# M105B.net
KiCad netlist of a schematic drawn in EAGLE
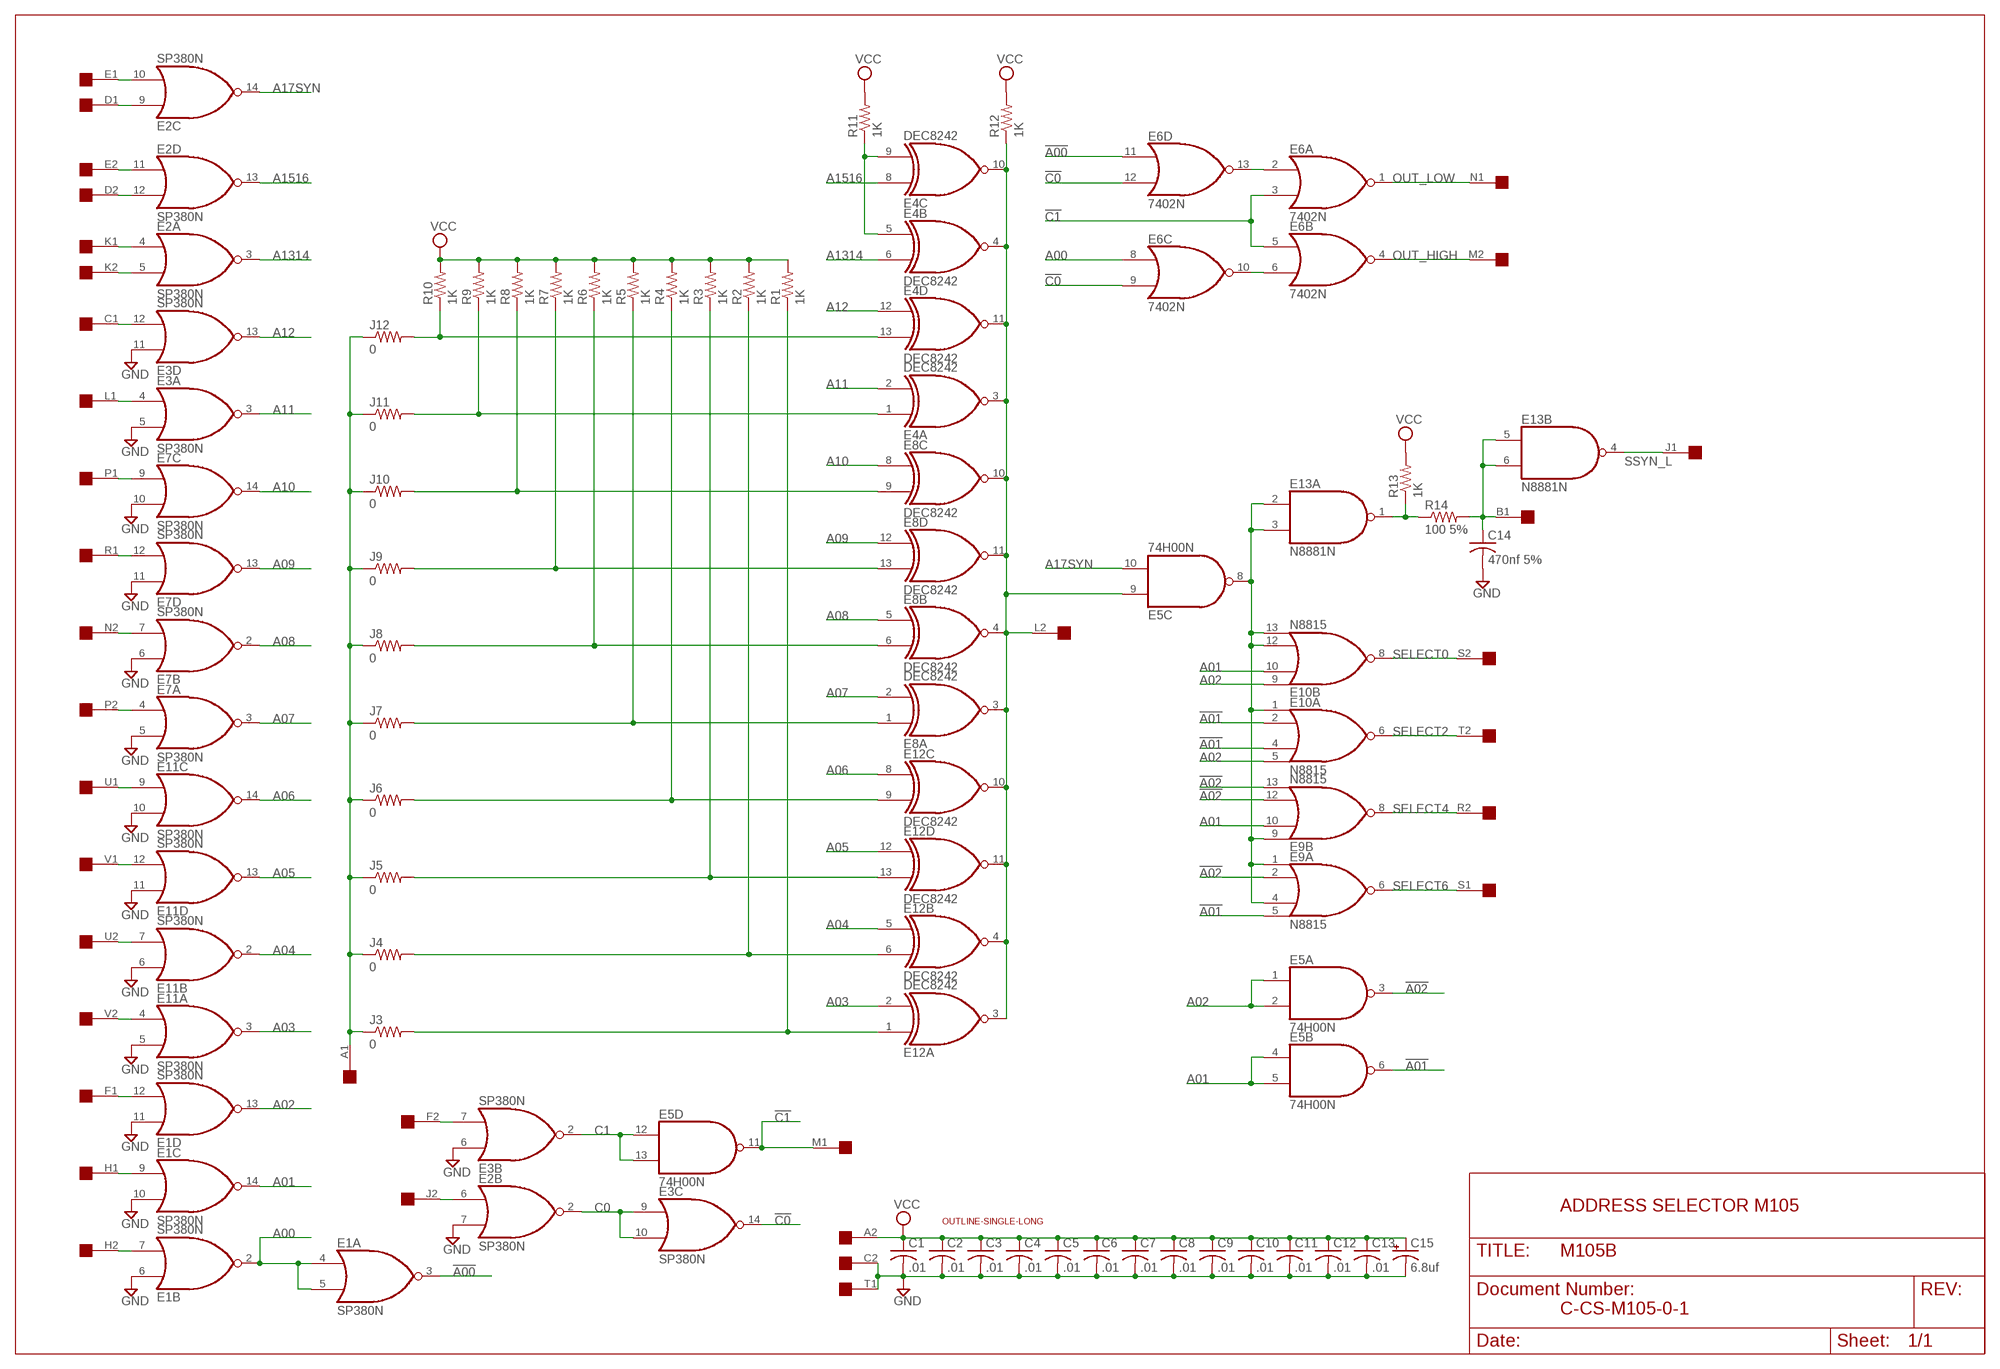
[diagram p0: schematic, sheet 1]

(export (version "E")
  (design (tool "Eeschema 10.0.6"))
  (components
    (comp (ref "C1")
      (value ".01")
      (footprint "eagle-import:C050-025X075")
      (libsource (lib "eagle-import") (part "C-US050-025X075"))
    )
    (comp (ref "C2")
      (value ".01")
      (footprint "eagle-import:C050-025X075")
      (libsource (lib "eagle-import") (part "C-US050-025X075"))
    )
    (comp (ref "C3")
      (value ".01")
      (footprint "eagle-import:C050-025X075")
      (libsource (lib "eagle-import") (part "C-US050-025X075"))
    )
    (comp (ref "C4")
      (value ".01")
      (footprint "eagle-import:C050-025X075")
      (libsource (lib "eagle-import") (part "C-US050-025X075"))
    )
    (comp (ref "C5")
      (value ".01")
      (footprint "eagle-import:C050-025X075")
      (libsource (lib "eagle-import") (part "C-US050-025X075"))
    )
    (comp (ref "C6")
      (value ".01")
      (footprint "eagle-import:C050-025X075")
      (libsource (lib "eagle-import") (part "C-US050-025X075"))
    )
    (comp (ref "C7")
      (value ".01")
      (footprint "eagle-import:C050-025X075")
      (libsource (lib "eagle-import") (part "C-US050-025X075"))
    )
    (comp (ref "C8")
      (value ".01")
      (footprint "eagle-import:C050-025X075")
      (libsource (lib "eagle-import") (part "C-US050-025X075"))
    )
    (comp (ref "C9")
      (value ".01")
      (footprint "eagle-import:C050-025X075")
      (libsource (lib "eagle-import") (part "C-US050-025X075"))
    )
    (comp (ref "C10")
      (value ".01")
      (footprint "eagle-import:C050-025X075")
      (libsource (lib "eagle-import") (part "C-US050-025X075"))
    )
    (comp (ref "C11")
      (value ".01")
      (footprint "eagle-import:C050-025X075")
      (libsource (lib "eagle-import") (part "C-US050-025X075"))
    )
    (comp (ref "C12")
      (value ".01")
      (footprint "eagle-import:C050-025X075")
      (libsource (lib "eagle-import") (part "C-US050-025X075"))
    )
    (comp (ref "C13")
      (value ".01")
      (footprint "eagle-import:C050-025X075")
      (libsource (lib "eagle-import") (part "C-US050-025X075"))
    )
    (comp (ref "C14")
      (value "470nf 5%")
      (footprint "eagle-import:C050-025X075")
      (libsource (lib "eagle-import") (part "C-US050-025X075"))
    )
    (comp (ref "C15")
      (value "6.8uf")
      (footprint "eagle-import:E15-5")
      (libsource (lib "eagle-import") (part "CPOL-USE15-5AXIAL"))
    )
    (comp (ref "E1")
      (value "SP380N")
      (footprint "eagle-import:DIL14")
      (libsource (lib "eagle-import") (part "SP380N"))
    )
    (comp (ref "E2")
      (value "SP380N")
      (footprint "eagle-import:DIL14")
      (libsource (lib "eagle-import") (part "SP380N"))
    )
    (comp (ref "E3")
      (value "SP380N")
      (footprint "eagle-import:DIL14")
      (libsource (lib "eagle-import") (part "SP380N"))
    )
    (comp (ref "E4")
      (value "DEC8242")
      (footprint "eagle-import:DIL14")
      (libsource (lib "eagle-import") (part "74266NLS"))
    )
    (comp (ref "E5")
      (value "74H00N")
      (footprint "eagle-import:DIL14")
      (libsource (lib "eagle-import") (part "7400NS"))
    )
    (comp (ref "E6")
      (value "7402N")
      (footprint "eagle-import:DIL14")
      (libsource (lib "eagle-import") (part "7402N"))
    )
    (comp (ref "E7")
      (value "SP380N")
      (footprint "eagle-import:DIL14")
      (libsource (lib "eagle-import") (part "SP380N"))
    )
    (comp (ref "E8")
      (value "DEC8242")
      (footprint "eagle-import:DIL14")
      (libsource (lib "eagle-import") (part "74266NLS"))
    )
    (comp (ref "E9")
      (value "N8815")
      (footprint "eagle-import:DIL14")
      (libsource (lib "eagle-import") (part "N8815"))
    )
    (comp (ref "E10")
      (value "N8815")
      (footprint "eagle-import:DIL14")
      (libsource (lib "eagle-import") (part "N8815"))
    )
    (comp (ref "E11")
      (value "SP380N")
      (footprint "eagle-import:DIL14")
      (libsource (lib "eagle-import") (part "SP380N"))
    )
    (comp (ref "E12")
      (value "DEC8242")
      (footprint "eagle-import:DIL14")
      (libsource (lib "eagle-import") (part "74266NLS"))
    )
    (comp (ref "E13")
      (value "N8881N")
      (footprint "eagle-import:DIL14")
      (libsource (lib "eagle-import") (part "N8881N"))
    )
    (comp (ref "J3")
      (value "0")
      (footprint "eagle-import:0207_10")
      (libsource (lib "eagle-import") (part "R-US_0207/10"))
    )
    (comp (ref "J4")
      (value "0")
      (footprint "eagle-import:0207_10")
      (libsource (lib "eagle-import") (part "R-US_0207/10"))
    )
    (comp (ref "J5")
      (value "0")
      (footprint "eagle-import:0207_10")
      (libsource (lib "eagle-import") (part "R-US_0207/10"))
    )
    (comp (ref "J6")
      (value "0")
      (footprint "eagle-import:0207_10")
      (libsource (lib "eagle-import") (part "R-US_0207/10"))
    )
    (comp (ref "J7")
      (value "0")
      (footprint "eagle-import:0207_10")
      (libsource (lib "eagle-import") (part "R-US_0207/10"))
    )
    (comp (ref "J8")
      (value "0")
      (footprint "eagle-import:0207_10")
      (libsource (lib "eagle-import") (part "R-US_0207/10"))
    )
    (comp (ref "J9")
      (value "0")
      (footprint "eagle-import:0207_10")
      (libsource (lib "eagle-import") (part "R-US_0207/10"))
    )
    (comp (ref "J10")
      (value "0")
      (footprint "eagle-import:0207_10")
      (libsource (lib "eagle-import") (part "R-US_0207/10"))
    )
    (comp (ref "J11")
      (value "0")
      (footprint "eagle-import:0207_10")
      (libsource (lib "eagle-import") (part "R-US_0207/10"))
    )
    (comp (ref "J12")
      (value "0")
      (footprint "eagle-import:0207_10")
      (libsource (lib "eagle-import") (part "R-US_0207/10"))
    )
    (comp (ref "R1")
      (value "1K")
      (footprint "eagle-import:0207_10")
      (libsource (lib "eagle-import") (part "R-US_0207/10"))
    )
    (comp (ref "R2")
      (value "1K")
      (footprint "eagle-import:0207_10")
      (libsource (lib "eagle-import") (part "R-US_0207/10"))
    )
    (comp (ref "R3")
      (value "1K")
      (footprint "eagle-import:0207_10")
      (libsource (lib "eagle-import") (part "R-US_0207/10"))
    )
    (comp (ref "R4")
      (value "1K")
      (footprint "eagle-import:0207_10")
      (libsource (lib "eagle-import") (part "R-US_0207/10"))
    )
    (comp (ref "R5")
      (value "1K")
      (footprint "eagle-import:0207_10")
      (libsource (lib "eagle-import") (part "R-US_0207/10"))
    )
    (comp (ref "R6")
      (value "1K")
      (footprint "eagle-import:0207_10")
      (libsource (lib "eagle-import") (part "R-US_0207/10"))
    )
    (comp (ref "R7")
      (value "1K")
      (footprint "eagle-import:0207_10")
      (libsource (lib "eagle-import") (part "R-US_0207/10"))
    )
    (comp (ref "R8")
      (value "1K")
      (footprint "eagle-import:0207_10")
      (libsource (lib "eagle-import") (part "R-US_0207/10"))
    )
    (comp (ref "R9")
      (value "1K")
      (footprint "eagle-import:0207_10")
      (libsource (lib "eagle-import") (part "R-US_0207/10"))
    )
    (comp (ref "R10")
      (value "1K")
      (footprint "eagle-import:0207_10")
      (libsource (lib "eagle-import") (part "R-US_0207/10"))
    )
    (comp (ref "R11")
      (value "1K")
      (footprint "eagle-import:0207_10")
      (libsource (lib "eagle-import") (part "R-US_0207/10"))
    )
    (comp (ref "R12")
      (value "1K")
      (footprint "eagle-import:0207_10")
      (libsource (lib "eagle-import") (part "R-US_0207/10"))
    )
    (comp (ref "R13")
      (value "1K")
      (footprint "eagle-import:0207_10")
      (libsource (lib "eagle-import") (part "R-US_0207/10"))
    )
    (comp (ref "R14")
      (value "100 5%")
      (footprint "eagle-import:0207_10")
      (libsource (lib "eagle-import") (part "R-US_0207/10"))
    )
    (comp (ref "U$1")
      (value "SINGLE")
      (footprint "eagle-import:EDGE-CON2")
      (libsource (lib "eagle-import") (part "SINGLE"))
    )
    (comp (ref "U$2")
      (value "OUTLINE-SINGLE-LONG")
      (footprint "eagle-import:SINGLE-LONG")
      (libsource (lib "eagle-import") (part "OUTLINE-SINGLE-LONG"))
    )
  )
  (nets
    (net (code "1") (name "/A00") (class "Default")
      (node (ref "E1") (pin "2") (pinfunction "O_2") (pintype "output"))
      (node (ref "E1") (pin "4") (pinfunction "I0_4") (pintype "input"))
      (node (ref "E1") (pin "5") (pinfunction "I1_5") (pintype "input"))
      (node (ref "E6") (pin "8") (pinfunction "I0_8") (pintype "input"))
    )
    (net (code "2") (name "/A01") (class "Default")
      (node (ref "E1") (pin "14") (pinfunction "O_14") (pintype "output"))
      (node (ref "E10") (pin "10") (pinfunction "I1_10") (pintype "input"))
      (node (ref "E5") (pin "4") (pinfunction "I0_4") (pintype "input"))
      (node (ref "E5") (pin "5") (pinfunction "I1_5") (pintype "input"))
      (node (ref "E9") (pin "10") (pinfunction "I1_10") (pintype "input"))
    )
    (net (code "3") (name "/A02") (class "Default")
      (node (ref "E1") (pin "13") (pinfunction "O_13") (pintype "output"))
      (node (ref "E10") (pin "5") (pinfunction "I3_5") (pintype "input"))
      (node (ref "E10") (pin "9") (pinfunction "I0_9") (pintype "input"))
      (node (ref "E5") (pin "1") (pinfunction "I0_1") (pintype "input"))
      (node (ref "E5") (pin "2") (pinfunction "I1_2") (pintype "input"))
    )
    (net (code "4") (name "/A03") (class "Default")
      (node (ref "E11") (pin "3") (pinfunction "O_3") (pintype "output"))
      (node (ref "E12") (pin "2") (pinfunction "I1_2") (pintype "input"))
    )
    (net (code "5") (name "/A04") (class "Default")
      (node (ref "E11") (pin "2") (pinfunction "O_2") (pintype "output"))
      (node (ref "E12") (pin "5") (pinfunction "I0_5") (pintype "input"))
    )
    (net (code "6") (name "/A05") (class "Default")
      (node (ref "E11") (pin "13") (pinfunction "O_13") (pintype "output"))
      (node (ref "E12") (pin "12") (pinfunction "I0_12") (pintype "input"))
    )
    (net (code "7") (name "/A06") (class "Default")
      (node (ref "E11") (pin "14") (pinfunction "O_14") (pintype "output"))
      (node (ref "E12") (pin "8") (pinfunction "I0_8") (pintype "input"))
    )
    (net (code "8") (name "/A07") (class "Default")
      (node (ref "E7") (pin "3") (pinfunction "O_3") (pintype "output"))
      (node (ref "E8") (pin "2") (pinfunction "I1_2") (pintype "input"))
    )
    (net (code "9") (name "/A08") (class "Default")
      (node (ref "E7") (pin "2") (pinfunction "O_2") (pintype "output"))
      (node (ref "E8") (pin "5") (pinfunction "I0_5") (pintype "input"))
    )
    (net (code "10") (name "/A09") (class "Default")
      (node (ref "E7") (pin "13") (pinfunction "O_13") (pintype "output"))
      (node (ref "E8") (pin "12") (pinfunction "I0_12") (pintype "input"))
    )
    (net (code "11") (name "/A10") (class "Default")
      (node (ref "E7") (pin "14") (pinfunction "O_14") (pintype "output"))
      (node (ref "E8") (pin "8") (pinfunction "I0_8") (pintype "input"))
    )
    (net (code "12") (name "/A11") (class "Default")
      (node (ref "E3") (pin "3") (pinfunction "O_3") (pintype "output"))
      (node (ref "E4") (pin "2") (pinfunction "I1_2") (pintype "input"))
    )
    (net (code "13") (name "/A12") (class "Default")
      (node (ref "E3") (pin "13") (pinfunction "O_13") (pintype "output"))
      (node (ref "E4") (pin "12") (pinfunction "I0_12") (pintype "input"))
    )
    (net (code "14") (name "/A17SYN") (class "Default")
      (node (ref "E2") (pin "14") (pinfunction "O_14") (pintype "output"))
      (node (ref "E5") (pin "10") (pinfunction "I1_10") (pintype "input"))
    )
    (net (code "15") (name "/A1314") (class "Default")
      (node (ref "E2") (pin "3") (pinfunction "O_3") (pintype "output"))
      (node (ref "E4") (pin "6") (pinfunction "I1_6") (pintype "input"))
    )
    (net (code "16") (name "/A1516") (class "Default")
      (node (ref "E2") (pin "13") (pinfunction "O_13") (pintype "output"))
      (node (ref "E4") (pin "8") (pinfunction "I0_8") (pintype "input"))
    )
    (net (code "17") (name "/C0") (class "Default")
      (node (ref "E2") (pin "2") (pinfunction "O_2") (pintype "output"))
      (node (ref "E3") (pin "10") (pinfunction "I1_10") (pintype "input"))
      (node (ref "E3") (pin "9") (pinfunction "I0_9") (pintype "input"))
    )
    (net (code "18") (name "/C1") (class "Default")
      (node (ref "E3") (pin "2") (pinfunction "O_2") (pintype "output"))
      (node (ref "E5") (pin "12") (pinfunction "I0_12") (pintype "input"))
      (node (ref "E5") (pin "13") (pinfunction "I1_13") (pintype "input"))
    )
    (net (code "19") (name "/OUT_HIGH") (class "Default")
      (node (ref "E6") (pin "4") (pinfunction "O_4") (pintype "output"))
      (node (ref "U$1") (pin "M2") (pinfunction "1_M2") (pintype "bidirectional"))
    )
    (net (code "20") (name "/OUT_LOW") (class "Default")
      (node (ref "E6") (pin "1") (pinfunction "O_1") (pintype "output"))
      (node (ref "U$1") (pin "N1") (pinfunction "1_N1") (pintype "bidirectional"))
    )
    (net (code "21") (name "/SELECT0") (class "Default")
      (node (ref "E10") (pin "8") (pinfunction "O_8") (pintype "output"))
      (node (ref "U$1") (pin "S2") (pinfunction "1_S2") (pintype "bidirectional"))
    )
    (net (code "22") (name "/SELECT2") (class "Default")
      (node (ref "E10") (pin "6") (pinfunction "O_6") (pintype "output"))
      (node (ref "U$1") (pin "T2") (pinfunction "1_T2") (pintype "bidirectional"))
    )
    (net (code "23") (name "/SELECT4") (class "Default")
      (node (ref "E9") (pin "8") (pinfunction "O_8") (pintype "output"))
      (node (ref "U$1") (pin "R2") (pinfunction "1_R2") (pintype "bidirectional"))
    )
    (net (code "24") (name "/SELECT6") (class "Default")
      (node (ref "E9") (pin "6") (pinfunction "O_6") (pintype "output"))
      (node (ref "U$1") (pin "S1") (pinfunction "1_S1") (pintype "bidirectional"))
    )
    (net (code "25") (name "/SSYN_L") (class "Default")
      (node (ref "E13") (pin "4") (pinfunction "O_4") (pintype "open_collector"))
      (node (ref "U$1") (pin "J1") (pinfunction "1_J1") (pintype "bidirectional"))
    )
    (net (code "26") (name "/~{A00}") (class "Default")
      (node (ref "E1") (pin "3") (pinfunction "O_3") (pintype "output"))
      (node (ref "E6") (pin "11") (pinfunction "I0_11") (pintype "input"))
    )
    (net (code "27") (name "/~{A01}") (class "Default")
      (node (ref "E10") (pin "2") (pinfunction "I1_2") (pintype "input"))
      (node (ref "E10") (pin "4") (pinfunction "I2_4") (pintype "input"))
      (node (ref "E5") (pin "6") (pinfunction "O_6") (pintype "output"))
      (node (ref "E9") (pin "5") (pinfunction "I3_5") (pintype "input"))
    )
    (net (code "28") (name "/~{A02}") (class "Default")
      (node (ref "E5") (pin "3") (pinfunction "O_3") (pintype "output"))
      (node (ref "E9") (pin "12") (pinfunction "I2_12") (pintype "input"))
      (node (ref "E9") (pin "13") (pinfunction "I3_13") (pintype "input"))
      (node (ref "E9") (pin "2") (pinfunction "I1_2") (pintype "input"))
    )
    (net (code "29") (name "/~{C0}") (class "Default")
      (node (ref "E3") (pin "14") (pinfunction "O_14") (pintype "output"))
      (node (ref "E6") (pin "12") (pinfunction "I1_12") (pintype "input"))
      (node (ref "E6") (pin "9") (pinfunction "I1_9") (pintype "input"))
    )
    (net (code "30") (name "/~{C1}") (class "Default")
      (node (ref "E5") (pin "11") (pinfunction "O_11") (pintype "output"))
      (node (ref "E6") (pin "3") (pinfunction "I1_3") (pintype "input"))
      (node (ref "E6") (pin "5") (pinfunction "I0_5") (pintype "input"))
      (node (ref "U$1") (pin "M1") (pinfunction "1_M1") (pintype "bidirectional"))
    )
    (net (code "31") (name "GND") (class "Default")
      (node (ref "C1") (pin "2") (pinfunction "2_2") (pintype "passive"))
      (node (ref "C10") (pin "2") (pinfunction "2_2") (pintype "passive"))
      (node (ref "C11") (pin "2") (pinfunction "2_2") (pintype "passive"))
      (node (ref "C12") (pin "2") (pinfunction "2_2") (pintype "passive"))
      (node (ref "C13") (pin "2") (pinfunction "2_2") (pintype "passive"))
      (node (ref "C14") (pin "2") (pinfunction "2_2") (pintype "passive"))
      (node (ref "C15") (pin "-") (pinfunction "-_-") (pintype "passive"))
      (node (ref "C2") (pin "2") (pinfunction "2_2") (pintype "passive"))
      (node (ref "C3") (pin "2") (pinfunction "2_2") (pintype "passive"))
      (node (ref "C4") (pin "2") (pinfunction "2_2") (pintype "passive"))
      (node (ref "C5") (pin "2") (pinfunction "2_2") (pintype "passive"))
      (node (ref "C6") (pin "2") (pinfunction "2_2") (pintype "passive"))
      (node (ref "C7") (pin "2") (pinfunction "2_2") (pintype "passive"))
      (node (ref "C8") (pin "2") (pinfunction "2_2") (pintype "passive"))
      (node (ref "C9") (pin "2") (pinfunction "2_2") (pintype "passive"))
      (node (ref "E1") (pin "10") (pinfunction "I1_10") (pintype "input"))
      (node (ref "E1") (pin "11") (pinfunction "I0_11") (pintype "input"))
      (node (ref "E1") (pin "6") (pinfunction "I0_6") (pintype "input"))
      (node (ref "E11") (pin "10") (pinfunction "I1_10") (pintype "input"))
      (node (ref "E11") (pin "11") (pinfunction "I0_11") (pintype "input"))
      (node (ref "E11") (pin "5") (pinfunction "I1_5") (pintype "input"))
      (node (ref "E11") (pin "6") (pinfunction "I0_6") (pintype "input"))
      (node (ref "E2") (pin "7") (pinfunction "I1_7") (pintype "input"))
      (node (ref "E3") (pin "11") (pinfunction "I0_11") (pintype "input"))
      (node (ref "E3") (pin "5") (pinfunction "I1_5") (pintype "input"))
      (node (ref "E3") (pin "6") (pinfunction "I0_6") (pintype "input"))
      (node (ref "E7") (pin "10") (pinfunction "I1_10") (pintype "input"))
      (node (ref "E7") (pin "11") (pinfunction "I0_11") (pintype "input"))
      (node (ref "E7") (pin "5") (pinfunction "I1_5") (pintype "input"))
      (node (ref "E7") (pin "6") (pinfunction "I0_6") (pintype "input"))
      (node (ref "U$1") (pin "C2") (pinfunction "1_C2") (pintype "bidirectional"))
      (node (ref "U$1") (pin "T1") (pinfunction "1_T1") (pintype "bidirectional"))
    )
    (net (code "32") (name "Net-(E1B-I1)") (class "Default")
      (node (ref "E1") (pin "7") (pinfunction "I1_7") (pintype "input"))
      (node (ref "U$1") (pin "H2") (pinfunction "1_H2") (pintype "bidirectional"))
    )
    (net (code "33") (name "Net-(E1C-I0)") (class "Default")
      (node (ref "E1") (pin "9") (pinfunction "I0_9") (pintype "input"))
      (node (ref "U$1") (pin "H1") (pinfunction "1_H1") (pintype "bidirectional"))
    )
    (net (code "34") (name "Net-(E1D-I1)") (class "Default")
      (node (ref "E1") (pin "12") (pinfunction "I1_12") (pintype "input"))
      (node (ref "U$1") (pin "F1") (pinfunction "1_F1") (pintype "bidirectional"))
    )
    (net (code "35") (name "Net-(E2A-I0)") (class "Default")
      (node (ref "E2") (pin "4") (pinfunction "I0_4") (pintype "input"))
      (node (ref "U$1") (pin "K1") (pinfunction "1_K1") (pintype "bidirectional"))
    )
    (net (code "36") (name "Net-(E2A-I1)") (class "Default")
      (node (ref "E2") (pin "5") (pinfunction "I1_5") (pintype "input"))
      (node (ref "U$1") (pin "K2") (pinfunction "1_K2") (pintype "bidirectional"))
    )
    (net (code "37") (name "Net-(E2B-I0)") (class "Default")
      (node (ref "E2") (pin "6") (pinfunction "I0_6") (pintype "input"))
      (node (ref "U$1") (pin "J2") (pinfunction "1_J2") (pintype "bidirectional"))
    )
    (net (code "38") (name "Net-(E2C-I0)") (class "Default")
      (node (ref "E2") (pin "9") (pinfunction "I0_9") (pintype "input"))
      (node (ref "U$1") (pin "D1") (pinfunction "1_D1") (pintype "bidirectional"))
    )
    (net (code "39") (name "Net-(E2C-I1)") (class "Default")
      (node (ref "E2") (pin "10") (pinfunction "I1_10") (pintype "input"))
      (node (ref "U$1") (pin "E1") (pinfunction "1_E1") (pintype "bidirectional"))
    )
    (net (code "40") (name "Net-(E2D-I0)") (class "Default")
      (node (ref "E2") (pin "11") (pinfunction "I0_11") (pintype "input"))
      (node (ref "U$1") (pin "E2") (pinfunction "1_E2") (pintype "bidirectional"))
    )
    (net (code "41") (name "Net-(E2D-I1)") (class "Default")
      (node (ref "E2") (pin "12") (pinfunction "I1_12") (pintype "input"))
      (node (ref "U$1") (pin "D2") (pinfunction "1_D2") (pintype "bidirectional"))
    )
    (net (code "42") (name "Net-(E3A-I0)") (class "Default")
      (node (ref "E3") (pin "4") (pinfunction "I0_4") (pintype "input"))
      (node (ref "U$1") (pin "L1") (pinfunction "1_L1") (pintype "bidirectional"))
    )
    (net (code "43") (name "Net-(E3B-I1)") (class "Default")
      (node (ref "E3") (pin "7") (pinfunction "I1_7") (pintype "input"))
      (node (ref "U$1") (pin "F2") (pinfunction "1_F2") (pintype "bidirectional"))
    )
    (net (code "44") (name "Net-(E3D-I1)") (class "Default")
      (node (ref "E3") (pin "12") (pinfunction "I1_12") (pintype "input"))
      (node (ref "U$1") (pin "C1") (pinfunction "1_C1") (pintype "bidirectional"))
    )
    (net (code "45") (name "Net-(E4A-I0)") (class "Default")
      (node (ref "E4") (pin "1") (pinfunction "I0_1") (pintype "input"))
      (node (ref "J11") (pin "2") (pinfunction "2_2") (pintype "passive"))
      (node (ref "R9") (pin "1") (pinfunction "1_1") (pintype "passive"))
    )
    (net (code "46") (name "Net-(E4B-I0)") (class "Default")
      (node (ref "E4") (pin "5") (pinfunction "I0_5") (pintype "input"))
      (node (ref "E4") (pin "9") (pinfunction "I1_9") (pintype "input"))
      (node (ref "R11") (pin "1") (pinfunction "1_1") (pintype "passive"))
    )
    (net (code "47") (name "Net-(E4D-I1)") (class "Default")
      (node (ref "E4") (pin "13") (pinfunction "I1_13") (pintype "input"))
      (node (ref "J12") (pin "2") (pinfunction "2_2") (pintype "passive"))
      (node (ref "R10") (pin "1") (pinfunction "1_1") (pintype "passive"))
    )
    (net (code "48") (name "Net-(E6A-I0)") (class "Default")
      (node (ref "E6") (pin "13") (pinfunction "O_13") (pintype "output"))
      (node (ref "E6") (pin "2") (pinfunction "I0_2") (pintype "input"))
    )
    (net (code "49") (name "Net-(E6B-I1)") (class "Default")
      (node (ref "E6") (pin "10") (pinfunction "O_10") (pintype "output"))
      (node (ref "E6") (pin "6") (pinfunction "I1_6") (pintype "input"))
    )
    (net (code "50") (name "Net-(E7A-I0)") (class "Default")
      (node (ref "E7") (pin "4") (pinfunction "I0_4") (pintype "input"))
      (node (ref "U$1") (pin "P2") (pinfunction "1_P2") (pintype "bidirectional"))
    )
    (net (code "51") (name "Net-(E7B-I1)") (class "Default")
      (node (ref "E7") (pin "7") (pinfunction "I1_7") (pintype "input"))
      (node (ref "U$1") (pin "N2") (pinfunction "1_N2") (pintype "bidirectional"))
    )
    (net (code "52") (name "Net-(E7C-I0)") (class "Default")
      (node (ref "E7") (pin "9") (pinfunction "I0_9") (pintype "input"))
      (node (ref "U$1") (pin "P1") (pinfunction "1_P1") (pintype "bidirectional"))
    )
    (net (code "53") (name "Net-(E7D-I1)") (class "Default")
      (node (ref "E7") (pin "12") (pinfunction "I1_12") (pintype "input"))
      (node (ref "U$1") (pin "R1") (pinfunction "1_R1") (pintype "bidirectional"))
    )
    (net (code "54") (name "Net-(E8A-I0)") (class "Default")
      (node (ref "E8") (pin "1") (pinfunction "I0_1") (pintype "input"))
      (node (ref "J7") (pin "2") (pinfunction "2_2") (pintype "passive"))
      (node (ref "R5") (pin "1") (pinfunction "1_1") (pintype "passive"))
    )
    (net (code "55") (name "Net-(E8B-I1)") (class "Default")
      (node (ref "E8") (pin "6") (pinfunction "I1_6") (pintype "input"))
      (node (ref "J8") (pin "2") (pinfunction "2_2") (pintype "passive"))
      (node (ref "R6") (pin "1") (pinfunction "1_1") (pintype "passive"))
    )
    (net (code "56") (name "Net-(E8C-I1)") (class "Default")
      (node (ref "E8") (pin "9") (pinfunction "I1_9") (pintype "input"))
      (node (ref "J10") (pin "2") (pinfunction "2_2") (pintype "passive"))
      (node (ref "R8") (pin "1") (pinfunction "1_1") (pintype "passive"))
    )
    (net (code "57") (name "Net-(E8D-I1)") (class "Default")
      (node (ref "E8") (pin "13") (pinfunction "I1_13") (pintype "input"))
      (node (ref "J9") (pin "2") (pinfunction "2_2") (pintype "passive"))
      (node (ref "R7") (pin "1") (pinfunction "1_1") (pintype "passive"))
    )
    (net (code "58") (name "Net-(E10A-I0)") (class "Default")
      (node (ref "E10") (pin "1") (pinfunction "I0_1") (pintype "input"))
      (node (ref "E10") (pin "12") (pinfunction "I2_12") (pintype "input"))
      (node (ref "E10") (pin "13") (pinfunction "I3_13") (pintype "input"))
      (node (ref "E13") (pin "2") (pinfunction "I0_2") (pintype "input"))
      (node (ref "E13") (pin "3") (pinfunction "I1_3") (pintype "input"))
      (node (ref "E5") (pin "8") (pinfunction "O_8") (pintype "output"))
      (node (ref "E9") (pin "1") (pinfunction "I0_1") (pintype "input"))
      (node (ref "E9") (pin "4") (pinfunction "I2_4") (pintype "input"))
      (node (ref "E9") (pin "9") (pinfunction "I0_9") (pintype "input"))
    )
    (net (code "59") (name "Net-(E11A-I0)") (class "Default")
      (node (ref "E11") (pin "4") (pinfunction "I0_4") (pintype "input"))
      (node (ref "U$1") (pin "V2") (pinfunction "1_V2") (pintype "bidirectional"))
    )
    (net (code "60") (name "Net-(E11B-I1)") (class "Default")
      (node (ref "E11") (pin "7") (pinfunction "I1_7") (pintype "input"))
      (node (ref "U$1") (pin "U2") (pinfunction "1_U2") (pintype "bidirectional"))
    )
    (net (code "61") (name "Net-(E11C-I0)") (class "Default")
      (node (ref "E11") (pin "9") (pinfunction "I0_9") (pintype "input"))
      (node (ref "U$1") (pin "U1") (pinfunction "1_U1") (pintype "bidirectional"))
    )
    (net (code "62") (name "Net-(E11D-I1)") (class "Default")
      (node (ref "E11") (pin "12") (pinfunction "I1_12") (pintype "input"))
      (node (ref "U$1") (pin "V1") (pinfunction "1_V1") (pintype "bidirectional"))
    )
    (net (code "63") (name "Net-(E12A-I0)") (class "Default")
      (node (ref "E12") (pin "1") (pinfunction "I0_1") (pintype "input"))
      (node (ref "J3") (pin "2") (pinfunction "2_2") (pintype "passive"))
      (node (ref "R1") (pin "1") (pinfunction "1_1") (pintype "passive"))
    )
    (net (code "64") (name "Net-(E12A-O)") (class "Default")
      (node (ref "E12") (pin "10") (pinfunction "O_10") (pintype "open_collector"))
      (node (ref "E12") (pin "11") (pinfunction "O_11") (pintype "open_collector"))
      (node (ref "E12") (pin "3") (pinfunction "O_3") (pintype "open_collector"))
      (node (ref "E12") (pin "4") (pinfunction "O_4") (pintype "open_collector"))
      (node (ref "E4") (pin "10") (pinfunction "O_10") (pintype "open_collector"))
      (node (ref "E4") (pin "11") (pinfunction "O_11") (pintype "open_collector"))
      (node (ref "E4") (pin "3") (pinfunction "O_3") (pintype "open_collector"))
      (node (ref "E4") (pin "4") (pinfunction "O_4") (pintype "open_collector"))
      (node (ref "E5") (pin "9") (pinfunction "I0_9") (pintype "input"))
      (node (ref "E8") (pin "10") (pinfunction "O_10") (pintype "open_collector"))
      (node (ref "E8") (pin "11") (pinfunction "O_11") (pintype "open_collector"))
      (node (ref "E8") (pin "3") (pinfunction "O_3") (pintype "open_collector"))
      (node (ref "E8") (pin "4") (pinfunction "O_4") (pintype "open_collector"))
      (node (ref "R12") (pin "1") (pinfunction "1_1") (pintype "passive"))
      (node (ref "U$1") (pin "L2") (pinfunction "1_L2") (pintype "bidirectional"))
    )
    (net (code "65") (name "Net-(E12B-I1)") (class "Default")
      (node (ref "E12") (pin "6") (pinfunction "I1_6") (pintype "input"))
      (node (ref "J4") (pin "2") (pinfunction "2_2") (pintype "passive"))
      (node (ref "R2") (pin "1") (pinfunction "1_1") (pintype "passive"))
    )
    (net (code "66") (name "Net-(E12C-I1)") (class "Default")
      (node (ref "E12") (pin "9") (pinfunction "I1_9") (pintype "input"))
      (node (ref "J6") (pin "2") (pinfunction "2_2") (pintype "passive"))
      (node (ref "R4") (pin "1") (pinfunction "1_1") (pintype "passive"))
    )
    (net (code "67") (name "Net-(E12D-I1)") (class "Default")
      (node (ref "E12") (pin "13") (pinfunction "I1_13") (pintype "input"))
      (node (ref "J5") (pin "2") (pinfunction "2_2") (pintype "passive"))
      (node (ref "R3") (pin "1") (pinfunction "1_1") (pintype "passive"))
    )
    (net (code "68") (name "Net-(E13A-O)") (class "Default")
      (node (ref "E13") (pin "1") (pinfunction "O_1") (pintype "open_collector"))
      (node (ref "R13") (pin "1") (pinfunction "1_1") (pintype "passive"))
      (node (ref "R14") (pin "1") (pinfunction "1_1") (pintype "passive"))
    )
    (net (code "69") (name "Net-(E13B-I0)") (class "Default")
      (node (ref "C14") (pin "1") (pinfunction "1_1") (pintype "passive"))
      (node (ref "E13") (pin "5") (pinfunction "I0_5") (pintype "input"))
      (node (ref "E13") (pin "6") (pinfunction "I1_6") (pintype "input"))
      (node (ref "R14") (pin "2") (pinfunction "2_2") (pintype "passive"))
      (node (ref "U$1") (pin "B1") (pinfunction "1_B1") (pintype "bidirectional"))
    )
    (net (code "70") (name "Net-(U$1A-1)") (class "Default")
      (node (ref "J10") (pin "1") (pinfunction "1_1") (pintype "passive"))
      (node (ref "J11") (pin "1") (pinfunction "1_1") (pintype "passive"))
      (node (ref "J12") (pin "1") (pinfunction "1_1") (pintype "passive"))
      (node (ref "J3") (pin "1") (pinfunction "1_1") (pintype "passive"))
      (node (ref "J4") (pin "1") (pinfunction "1_1") (pintype "passive"))
      (node (ref "J5") (pin "1") (pinfunction "1_1") (pintype "passive"))
      (node (ref "J6") (pin "1") (pinfunction "1_1") (pintype "passive"))
      (node (ref "J7") (pin "1") (pinfunction "1_1") (pintype "passive"))
      (node (ref "J8") (pin "1") (pinfunction "1_1") (pintype "passive"))
      (node (ref "J9") (pin "1") (pinfunction "1_1") (pintype "passive"))
      (node (ref "U$1") (pin "A1") (pinfunction "1_A1") (pintype "bidirectional"))
    )
    (net (code "71") (name "VCC") (class "Default")
      (node (ref "C1") (pin "1") (pinfunction "1_1") (pintype "passive"))
      (node (ref "C10") (pin "1") (pinfunction "1_1") (pintype "passive"))
      (node (ref "C11") (pin "1") (pinfunction "1_1") (pintype "passive"))
      (node (ref "C12") (pin "1") (pinfunction "1_1") (pintype "passive"))
      (node (ref "C13") (pin "1") (pinfunction "1_1") (pintype "passive"))
      (node (ref "C15") (pin "+") (pinfunction "+_+") (pintype "passive"))
      (node (ref "C2") (pin "1") (pinfunction "1_1") (pintype "passive"))
      (node (ref "C3") (pin "1") (pinfunction "1_1") (pintype "passive"))
      (node (ref "C4") (pin "1") (pinfunction "1_1") (pintype "passive"))
      (node (ref "C5") (pin "1") (pinfunction "1_1") (pintype "passive"))
      (node (ref "C6") (pin "1") (pinfunction "1_1") (pintype "passive"))
      (node (ref "C7") (pin "1") (pinfunction "1_1") (pintype "passive"))
      (node (ref "C8") (pin "1") (pinfunction "1_1") (pintype "passive"))
      (node (ref "C9") (pin "1") (pinfunction "1_1") (pintype "passive"))
      (node (ref "R1") (pin "2") (pinfunction "2_2") (pintype "passive"))
      (node (ref "R10") (pin "2") (pinfunction "2_2") (pintype "passive"))
      (node (ref "R11") (pin "2") (pinfunction "2_2") (pintype "passive"))
      (node (ref "R12") (pin "2") (pinfunction "2_2") (pintype "passive"))
      (node (ref "R13") (pin "2") (pinfunction "2_2") (pintype "passive"))
      (node (ref "R2") (pin "2") (pinfunction "2_2") (pintype "passive"))
      (node (ref "R3") (pin "2") (pinfunction "2_2") (pintype "passive"))
      (node (ref "R4") (pin "2") (pinfunction "2_2") (pintype "passive"))
      (node (ref "R5") (pin "2") (pinfunction "2_2") (pintype "passive"))
      (node (ref "R6") (pin "2") (pinfunction "2_2") (pintype "passive"))
      (node (ref "R7") (pin "2") (pinfunction "2_2") (pintype "passive"))
      (node (ref "R8") (pin "2") (pinfunction "2_2") (pintype "passive"))
      (node (ref "R9") (pin "2") (pinfunction "2_2") (pintype "passive"))
      (node (ref "U$1") (pin "A2") (pinfunction "1_A2") (pintype "bidirectional"))
    )
  )
)
